# monitor_waterpressure.net
KiCad netlist of a schematic drawn in Altium Designer
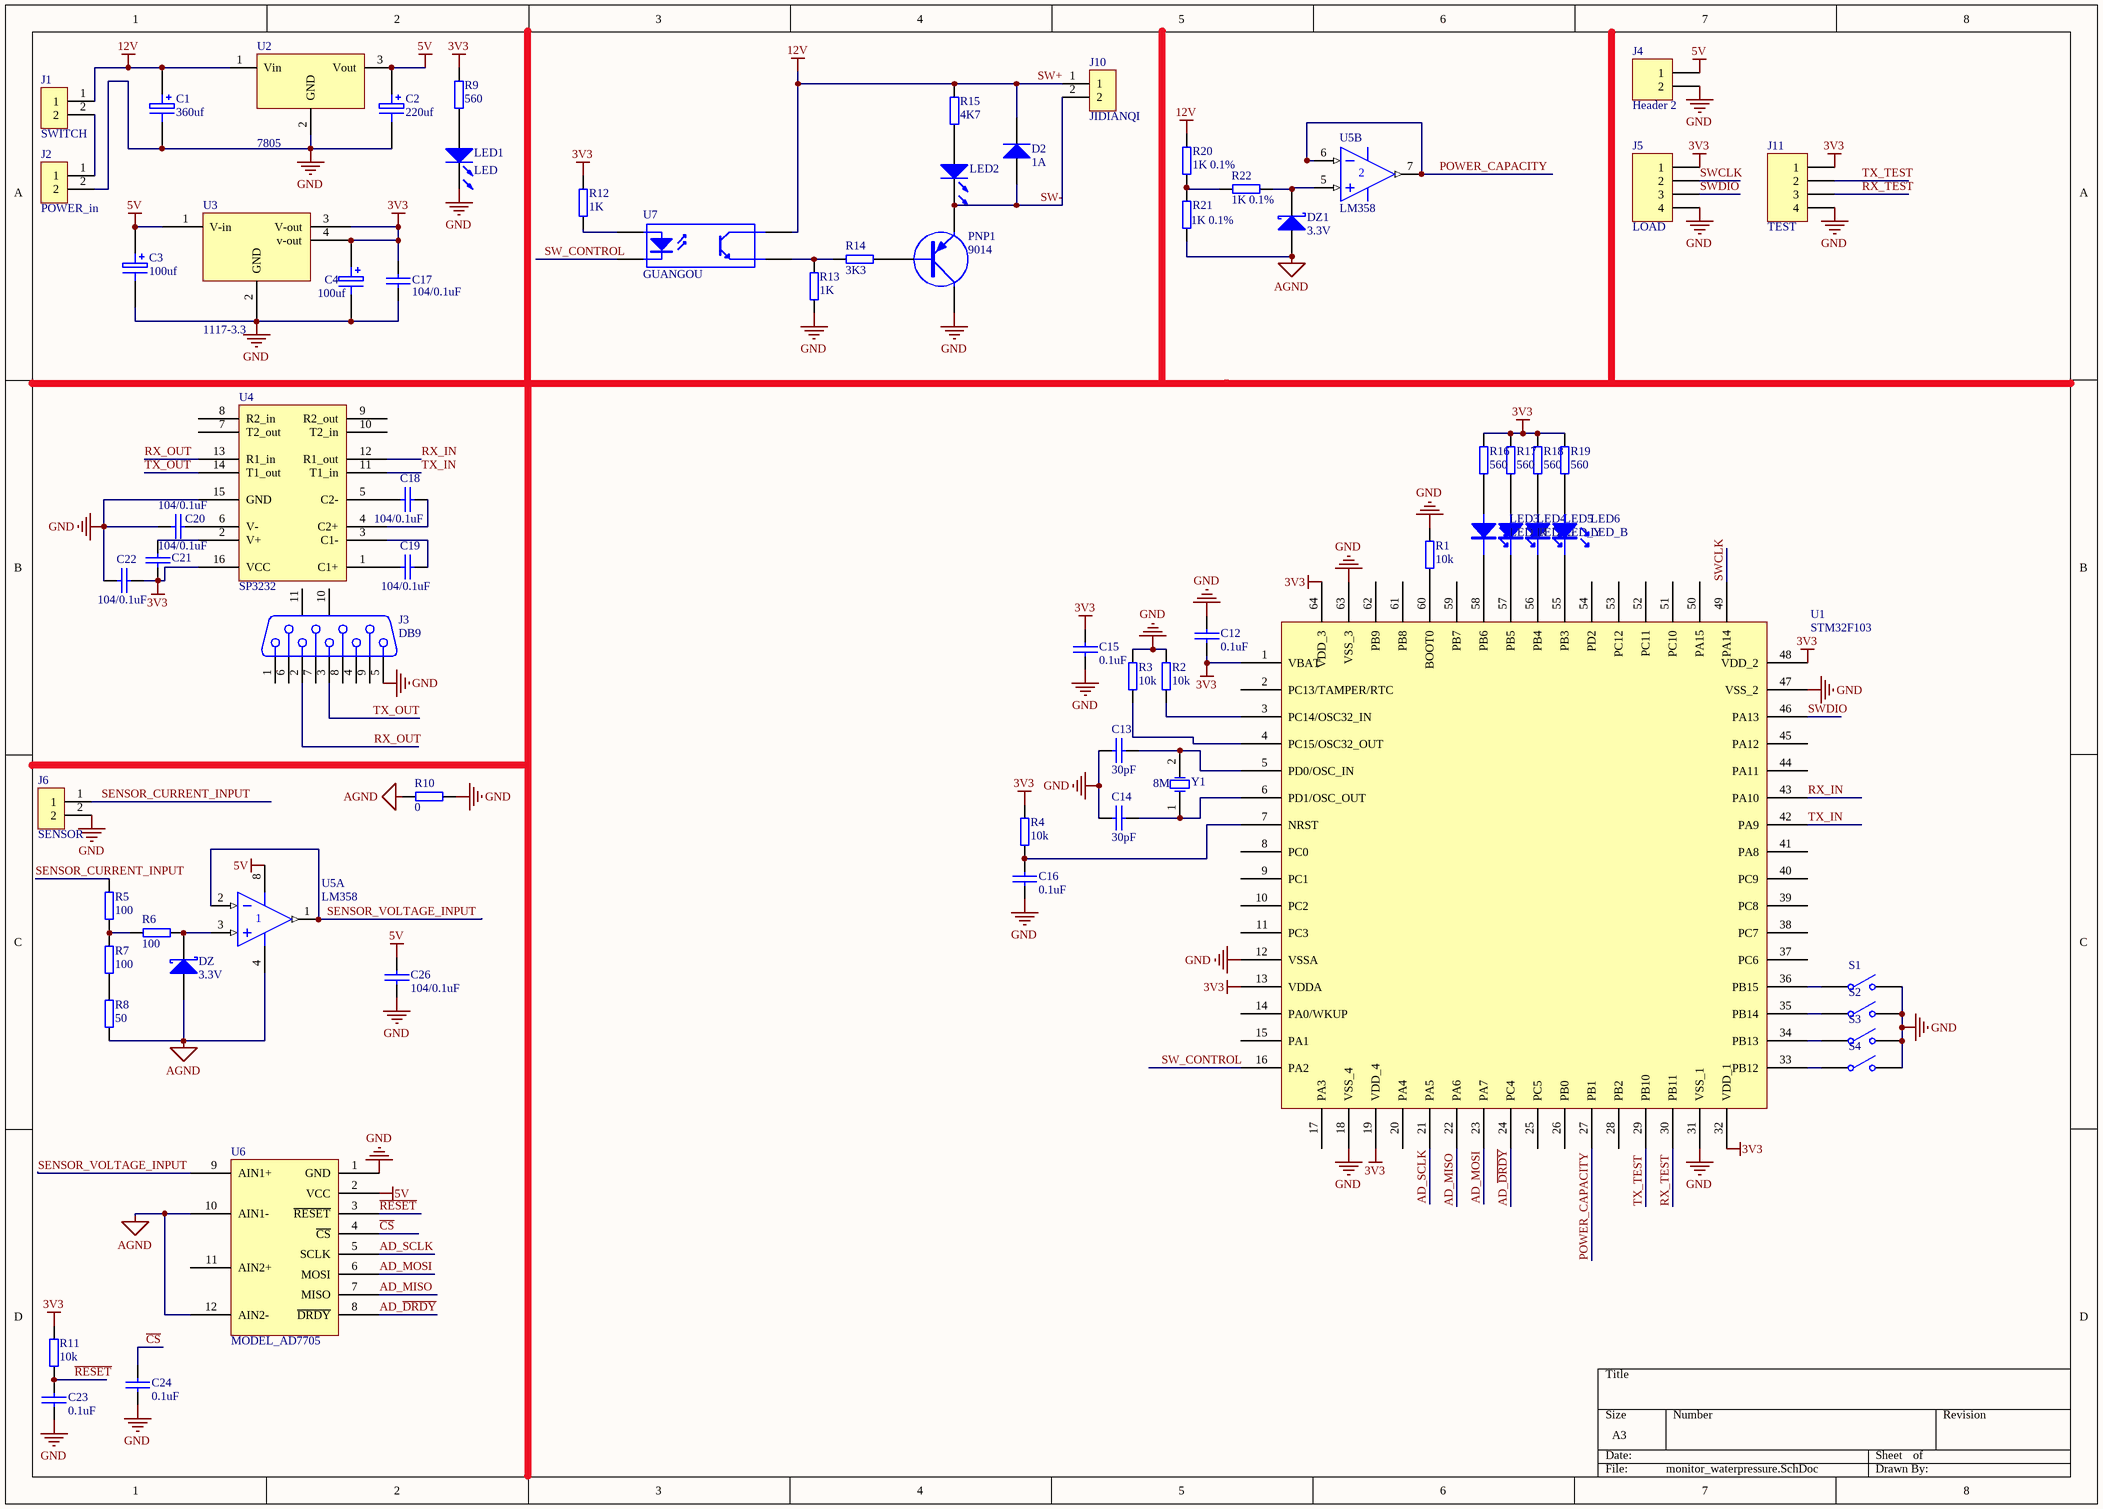
[diagram p0: monitor_waterpressure.SchDoc]

(export (version "E")
  (design (tool "Eeschema 10.0.6"))
  (components
    (comp (ref "C1")
      (value "360uf")
      (footprint "RAD-200-1")
      (description "Electrolytic Capacitor")
      (libsource (lib "PRJ_智能泊车") (part "ELECTRO1"))
    )
    (comp (ref "C2")
      (value "220uf")
      (footprint "RAD-200-1")
      (description "Electrolytic Capacitor")
      (libsource (lib "PRJ_智能泊车") (part "ELECTRO1"))
    )
    (comp (ref "C3")
      (value "100uf")
      (footprint "RAD-200-1")
      (description "Electrolytic Capacitor")
      (libsource (lib "PRJ_智能泊车") (part "ELECTRO1"))
    )
    (comp (ref "C4")
      (value "100uf")
      (footprint "RAD-200-1")
      (description "Electrolytic Capacitor")
      (libsource (lib "PRJ_智能泊车") (part "ELECTRO1"))
    )
    (comp (ref "C12")
      (value "0.1uF")
      (footprint "0805")
      (libsource (lib "hujian-sch2016-05-07") (part "cap"))
    )
    (comp (ref "C13") (value "30pF") (footprint "0805") (libsource (lib "hujian-sch2016-05-07") (part "cap")))
    (comp (ref "C14") (value "30pF") (footprint "0805") (libsource (lib "hujian-sch2016-05-07") (part "cap")))
    (comp (ref "C15")
      (value "0.1uF")
      (footprint "0805")
      (libsource (lib "hujian-sch2016-05-07") (part "cap"))
    )
    (comp (ref "C16")
      (value "0.1uF")
      (footprint "0805")
      (libsource (lib "hujian-sch2016-05-07") (part "cap"))
    )
    (comp (ref "C17")
      (value "104/0.1uF")
      (footprint "0805")
      (libsource (lib "hujian-sch2016-05-07") (part "cap"))
    )
    (comp (ref "C18")
      (value "104/0.1uF")
      (footprint "0805")
      (libsource (lib "hujian-sch2016-05-07") (part "cap"))
    )
    (comp (ref "C19")
      (value "104/0.1uF")
      (footprint "0805")
      (libsource (lib "hujian-sch2016-05-07") (part "cap"))
    )
    (comp (ref "C20")
      (value "104/0.1uF")
      (footprint "0805")
      (libsource (lib "hujian-sch2016-05-07") (part "cap"))
    )
    (comp (ref "C21")
      (value "104/0.1uF")
      (footprint "0805")
      (libsource (lib "hujian-sch2016-05-07") (part "cap"))
    )
    (comp (ref "C22")
      (value "104/0.1uF")
      (footprint "0805")
      (libsource (lib "hujian-sch2016-05-07") (part "cap"))
    )
    (comp (ref "C23")
      (value "0.1uF")
      (footprint "0805")
      (libsource (lib "hujian-sch2016-05-07") (part "cap"))
    )
    (comp (ref "C24")
      (value "0.1uF")
      (footprint "0805")
      (libsource (lib "hujian-sch2016-05-07") (part "cap"))
    )
    (comp (ref "C26")
      (value "104/0.1uF")
      (footprint "0805")
      (libsource (lib "hujian-sch2016-05-07") (part "cap"))
    )
    (comp (ref "D2")
      (value "1A")
      (footprint "ERJIGUAN-1.1MM")
      (libsource (lib "hujian-sch2016-05-07") (part "DIODE"))
    )
    (comp (ref "DZ")
      (value "3.3V")
      (footprint "ERJIGUAN-5")
      (description "Schottky Rectifier")
      (fields (field (name "PUBLISHER") "Altium Limited"))
      (libsource (lib "hujian-sch2016-05-07") (part "Diode_DZ"))
    )
    (comp (ref "DZ1")
      (value "3.3V")
      (footprint "ERJIGUAN-5")
      (description "Schottky Rectifier")
      (fields (field (name "PUBLISHER") "Altium Limited"))
      (libsource (lib "hujian-sch2016-05-07") (part "Diode_DZ"))
    )
    (comp (ref "J1") (value "SWITCH") (footprint "CON2_7.62MM") (libsource (lib "") (part "CON2_1")))
    (comp (ref "J2") (value "POWER_in") (footprint "CON2-100mil-XH") (libsource (lib "") (part "CON2_1")))
    (comp (ref "J3") (value "DB9") (footprint "DB9") (libsource (lib "hujian-sch2016-05-07") (part "DB9")))
    (comp (ref "J4")
      (value "Header 2")
      (footprint "HDR1X2")
      (description "Header, 2-Pin")
      (fields (field (name "PUBLISHER") "Altium Limited"))
      (libsource (lib "Miscellaneous Connectors") (part "Header 2"))
    )
    (comp (ref "J5")
      (value "LOAD")
      (footprint "HDR1X4")
      (description "Header, 4-Pin")
      (fields (field (name "PUBLISHER") "Altium Limited"))
      (libsource (lib "Miscellaneous Connectors") (part "Header 4"))
    )
    (comp (ref "J6") (value "SENSOR") (footprint "CON2-200") (libsource (lib "") (part "CON2_1")))
    (comp (ref "J10")
      (value "JIDIANQI")
      (footprint "CN2_S")
      (libsource (lib "hujian-sch2016-05-07") (part "CON2"))
    )
    (comp (ref "J11")
      (value "TEST")
      (footprint "HDR1X4")
      (description "Header, 4-Pin")
      (fields (field (name "PUBLISHER") "Altium Limited"))
      (libsource (lib "Miscellaneous Connectors") (part "Header 4"))
    )
    (comp (ref "LED1")
      (value "LED")
      (footprint "LED-0805")
      (fields (field (name "PUBLISHER") "Altium Limited"))
      (libsource (lib "hujian-sch2016-05-07") (part "LED"))
    )
    (comp (ref "LED2")
      (value "LED-AK")
      (footprint "LED-0805")
      (fields (field (name "PUBLISHER") "Altium Limited"))
      (libsource (lib "hujian-sch2016-05-07") (part "LED"))
    )
    (comp (ref "LED3") (value "LED_R") (footprint "LED-0805") (libsource (lib "PRJ_智能泊车") (part "LED")))
    (comp (ref "LED4") (value "LED_G") (footprint "LED-0805") (libsource (lib "PRJ_智能泊车") (part "LED")))
    (comp (ref "LED5") (value "LED_Y") (footprint "LED-0805") (libsource (lib "PRJ_智能泊车") (part "LED")))
    (comp (ref "LED6") (value "LED_B") (footprint "LED-0805") (libsource (lib "PRJ_智能泊车") (part "LED")))
    (comp (ref "PNP1")
      (value "9014")
      (footprint "PNP")
      (libsource (lib "hujian-sch2016-05-07") (part "PNP_123"))
    )
    (comp (ref "R1")
      (value "10k")
      (footprint "0805")
      (libsource (lib "hujian-sch2016-05-07") (part "RES2-2"))
    )
    (comp (ref "R2")
      (value "10k")
      (footprint "0805")
      (libsource (lib "hujian-sch2016-05-07") (part "RES2-2"))
    )
    (comp (ref "R3")
      (value "10k")
      (footprint "0805")
      (libsource (lib "hujian-sch2016-05-07") (part "RES2-2"))
    )
    (comp (ref "R4")
      (value "10k")
      (footprint "0805")
      (libsource (lib "hujian-sch2016-05-07") (part "RES2-2"))
    )
    (comp (ref "R5")
      (value "100")
      (footprint "0805")
      (libsource (lib "hujian-sch2016-05-07") (part "RES2-2"))
    )
    (comp (ref "R6")
      (value "100")
      (footprint "0805")
      (libsource (lib "hujian-sch2016-05-07") (part "RES2-2"))
    )
    (comp (ref "R7")
      (value "100")
      (footprint "0805")
      (libsource (lib "hujian-sch2016-05-07") (part "RES2-2"))
    )
    (comp (ref "R8") (value "50") (footprint "0805") (libsource (lib "hujian-sch2016-05-07") (part "RES2-2")))
    (comp (ref "R9")
      (value "560")
      (footprint "0805")
      (libsource (lib "hujian-sch2016-05-07") (part "RES2-2"))
    )
    (comp (ref "R10") (value "0") (footprint "0805") (libsource (lib "hujian-sch2016-05-07") (part "RES2-2")))
    (comp (ref "R11")
      (value "10k")
      (footprint "0805")
      (libsource (lib "hujian-sch2016-05-07") (part "RES2-2"))
    )
    (comp (ref "R12")
      (value "1K")
      (footprint "0805")
      (libsource (lib "hujian-sch2016-05-07") (part "RES2-2"))
    )
    (comp (ref "R13")
      (value "1K")
      (footprint "0805")
      (libsource (lib "hujian-sch2016-05-07") (part "RES2-2"))
    )
    (comp (ref "R14")
      (value "3K3")
      (footprint "0805")
      (libsource (lib "hujian-sch2016-05-07") (part "RES2-2"))
    )
    (comp (ref "R15")
      (value "4K7")
      (footprint "0805")
      (libsource (lib "hujian-sch2016-05-07") (part "RES2-2"))
    )
    (comp (ref "R16")
      (value "560")
      (footprint "0805")
      (libsource (lib "hujian-sch2016-05-07") (part "RES2-2"))
    )
    (comp (ref "R17")
      (value "560")
      (footprint "0805")
      (libsource (lib "hujian-sch2016-05-07") (part "RES2-2"))
    )
    (comp (ref "R18")
      (value "560")
      (footprint "0805")
      (libsource (lib "hujian-sch2016-05-07") (part "RES2-2"))
    )
    (comp (ref "R19")
      (value "560")
      (footprint "0805")
      (libsource (lib "hujian-sch2016-05-07") (part "RES2-2"))
    )
    (comp (ref "R20")
      (value "1K 0.1%")
      (footprint "0805")
      (libsource (lib "hujian-sch2016-05-07") (part "RES2-2"))
    )
    (comp (ref "R21")
      (value "1K 0.1%")
      (footprint "0805")
      (libsource (lib "hujian-sch2016-05-07") (part "RES2-2"))
    )
    (comp (ref "R22")
      (value "1K 0.1%")
      (footprint "0805")
      (libsource (lib "hujian-sch2016-05-07") (part "RES2-2"))
    )
    (comp (ref "S1")
      (value "SW-SPST")
      (footprint "SW_SPST")
      (description "Single-Pole, Single-Throw Switch")
      (fields (field (name "PUBLISHER") "Altium Limited"))
      (libsource (lib "Miscellaneous Devices") (part "SW-SPST"))
    )
    (comp (ref "S2")
      (value "SW-SPST")
      (footprint "SW_SPST")
      (description "Single-Pole, Single-Throw Switch")
      (fields (field (name "PUBLISHER") "Altium Limited"))
      (libsource (lib "Miscellaneous Devices") (part "SW-SPST"))
    )
    (comp (ref "S3")
      (value "SW-SPST")
      (footprint "SW_SPST")
      (description "Single-Pole, Single-Throw Switch")
      (fields (field (name "PUBLISHER") "Altium Limited"))
      (libsource (lib "Miscellaneous Devices") (part "SW-SPST"))
    )
    (comp (ref "S4")
      (value "SW-SPST")
      (footprint "SW_SPST")
      (description "Single-Pole, Single-Throw Switch")
      (fields (field (name "PUBLISHER") "Altium Limited"))
      (libsource (lib "Miscellaneous Devices") (part "SW-SPST"))
    )
    (comp (ref "U1")
      (value "STM32F103")
      (footprint "LQFP-64")
      (libsource (lib "hujian-sch2016-05-07") (part "STM32F103"))
    )
    (comp (ref "U2")
      (value "7805")
      (footprint "TO220")
      (libsource (lib "hujian-sch2016-05-07") (part "7805"))
    )
    (comp (ref "U3")
      (value "1117-3.3")
      (footprint "lm1117-3.3")
      (libsource (lib "hujian-sch2016-05-07") (part "1117-3.3"))
    )
    (comp (ref "U4")
      (value "SP3232")
      (footprint "SO-16")
      (description "U")
      (libsource (lib "hujian-sch2016-05-07") (part "MAX232"))
    )
    (comp (ref "U5")
      (value "LM358")
      (footprint "SO-8")
      (libsource (lib "hujian-sch2016-05-07") (part "LM358"))
    )
    (comp (ref "U6") (value "MODEL_AD7705") (libsource (lib "hujian-sch2016-05-07") (part "MODEL_AD7705")))
    (comp (ref "U7")
      (value "GUANGOU")
      (footprint "TLP521")
      (libsource (lib "hujian-sch2016-05-07") (part "GUANGOU"))
    )
    (comp (ref "Y1") (value "8M") (footprint "XTAL1") (libsource (lib "hujian-sch2016-05-07") (part "晶振")))
  )
  (nets
    (net (code "1") (name "/AD_MISO") (class "Default")
      (node (ref "U1") (pin "22") (pinfunction "PA6_22") (pintype "passive"))
      (node (ref "U6") (pin "7") (pinfunction "MISO_7") (pintype "passive"))
    )
    (net (code "2") (name "/AD_MOSI") (class "Default")
      (node (ref "U1") (pin "23") (pinfunction "PA7_23") (pintype "passive"))
      (node (ref "U6") (pin "6") (pinfunction "MOSI_6") (pintype "passive"))
    )
    (net (code "3") (name "/AD_SCLK") (class "Default")
      (node (ref "U1") (pin "21") (pinfunction "PA5_21") (pintype "passive"))
      (node (ref "U6") (pin "5") (pinfunction "SCLK_5") (pintype "passive"))
    )
    (net (code "4") (name "/AD_~{DRDY}") (class "Default")
      (node (ref "U1") (pin "24") (pinfunction "PC4_24") (pintype "passive"))
      (node (ref "U6") (pin "8") (pinfunction "~{DRDY}_8") (pintype "passive"))
    )
    (net (code "5") (name "/POWER_CAPACITY") (class "Default")
      (node (ref "U1") (pin "27") (pinfunction "PB1_27") (pintype "passive"))
      (node (ref "U5") (pin "6") (pinfunction "IN-_6") (pintype "input"))
      (node (ref "U5") (pin "7") (pinfunction "OUT_7") (pintype "output"))
    )
    (net (code "6") (name "/RX_IN") (class "Default")
      (node (ref "U1") (pin "43") (pinfunction "PA10_43") (pintype "passive"))
      (node (ref "U4") (pin "12") (pinfunction "R1_out_12") (pintype "passive"))
    )
    (net (code "7") (name "/RX_OUT") (class "Default")
      (node (ref "J3") (pin "2") (pinfunction "2_2") (pintype "passive"))
      (node (ref "U4") (pin "13") (pinfunction "R1_in_13") (pintype "passive"))
    )
    (net (code "8") (name "/RX_TEST") (class "Default")
      (node (ref "J11") (pin "3") (pinfunction "3_3") (pintype "passive"))
      (node (ref "U1") (pin "30") (pinfunction "PB11_30") (pintype "passive"))
    )
    (net (code "9") (name "/SENSOR_CURRENT_INPUT") (class "Default")
      (node (ref "J6") (pin "1") (pinfunction "1_1") (pintype "passive"))
      (node (ref "R5") (pin "2") (pinfunction "2_2") (pintype "passive"))
    )
    (net (code "10") (name "/SENSOR_VOLTAGE_INPUT") (class "Default")
      (node (ref "U5") (pin "1") (pinfunction "1_1") (pintype "output"))
      (node (ref "U5") (pin "2") (pinfunction "IN-_2") (pintype "input"))
      (node (ref "U6") (pin "9") (pinfunction "AIN1+_9") (pintype "passive"))
    )
    (net (code "11") (name "/SW-") (class "Default")
      (node (ref "D2") (pin "1") (pinfunction "1_1") (pintype "passive"))
      (node (ref "J10") (pin "2") (pinfunction "2_2") (pintype "passive"))
      (node (ref "LED2") (pin "K") (pinfunction "K_K") (pintype "passive"))
      (node (ref "PNP1") (pin "2") (pinfunction "E_2") (pintype "passive"))
    )
    (net (code "12") (name "/SWCLK") (class "Default")
      (node (ref "J5") (pin "2") (pinfunction "2_2") (pintype "passive"))
      (node (ref "U1") (pin "49") (pinfunction "PA14_49") (pintype "passive"))
    )
    (net (code "13") (name "/SWDIO") (class "Default")
      (node (ref "J5") (pin "3") (pinfunction "3_3") (pintype "passive"))
      (node (ref "U1") (pin "46") (pinfunction "PA13_46") (pintype "passive"))
    )
    (net (code "14") (name "/SW_CONTROL") (class "Default")
      (node (ref "U1") (pin "16") (pinfunction "PA2_16") (pintype "passive"))
      (node (ref "U7") (pin "2") (pinfunction "K_2") (pintype "passive"))
    )
    (net (code "15") (name "/TX_IN") (class "Default")
      (node (ref "U1") (pin "42") (pinfunction "PA9_42") (pintype "passive"))
      (node (ref "U4") (pin "11") (pinfunction "T1_in_11") (pintype "passive"))
    )
    (net (code "16") (name "/TX_OUT") (class "Default")
      (node (ref "J3") (pin "3") (pinfunction "3_3") (pintype "passive"))
      (node (ref "U4") (pin "14") (pinfunction "T1_out_14") (pintype "passive"))
    )
    (net (code "17") (name "/TX_TEST") (class "Default")
      (node (ref "J11") (pin "2") (pinfunction "2_2") (pintype "passive"))
      (node (ref "U1") (pin "29") (pinfunction "PB10_29") (pintype "passive"))
    )
    (net (code "18") (name "/~{CS}") (class "Default")
      (node (ref "C24") (pin "1") (pinfunction "1_1") (pintype "passive"))
      (node (ref "U6") (pin "4") (pinfunction "~{CS}_4") (pintype "passive"))
    )
    (net (code "19") (name "/~{RESET}") (class "Default")
      (node (ref "C23") (pin "1") (pinfunction "1_1") (pintype "passive"))
      (node (ref "R11") (pin "1") (pinfunction "1_1") (pintype "passive"))
      (node (ref "U6") (pin "3") (pinfunction "~{RESET}_3") (pintype "passive"))
    )
    (net (code "20") (name "3V3") (class "Default")
      (node (ref "C12") (pin "2") (pinfunction "2_2") (pintype "passive"))
      (node (ref "C15") (pin "1") (pinfunction "1_1") (pintype "passive"))
      (node (ref "C17") (pin "1") (pinfunction "1_1") (pintype "passive"))
      (node (ref "C21") (pin "1") (pinfunction "1_1") (pintype "passive"))
      (node (ref "C22") (pin "2") (pinfunction "2_2") (pintype "passive"))
      (node (ref "C4") (pin "1") (pinfunction "1_1") (pintype "passive"))
      (node (ref "J11") (pin "1") (pinfunction "1_1") (pintype "passive"))
      (node (ref "J5") (pin "1") (pinfunction "1_1") (pintype "passive"))
      (node (ref "R11") (pin "2") (pinfunction "2_2") (pintype "passive"))
      (node (ref "R12") (pin "2") (pinfunction "2_2") (pintype "passive"))
      (node (ref "R16") (pin "1") (pinfunction "1_1") (pintype "passive"))
      (node (ref "R17") (pin "1") (pinfunction "1_1") (pintype "passive"))
      (node (ref "R18") (pin "2") (pinfunction "2_2") (pintype "passive"))
      (node (ref "R19") (pin "2") (pinfunction "2_2") (pintype "passive"))
      (node (ref "R4") (pin "2") (pinfunction "2_2") (pintype "passive"))
      (node (ref "R9") (pin "2") (pinfunction "2_2") (pintype "passive"))
      (node (ref "U1") (pin "1") (pinfunction "VBAT_1") (pintype "passive"))
      (node (ref "U1") (pin "13") (pinfunction "VDDA_13") (pintype "passive"))
      (node (ref "U1") (pin "19") (pinfunction "VDD_4_19") (pintype "passive"))
      (node (ref "U1") (pin "32") (pinfunction "VDD_1_32") (pintype "passive"))
      (node (ref "U1") (pin "48") (pinfunction "VDD_2_48") (pintype "passive"))
      (node (ref "U1") (pin "64") (pinfunction "VDD_3_64") (pintype "passive"))
      (node (ref "U3") (pin "3") (pinfunction "V-out_3") (pintype "passive"))
      (node (ref "U3") (pin "4") (pinfunction "v-out_4") (pintype "passive"))
      (node (ref "U4") (pin "16") (pinfunction "VCC_16") (pintype "passive"))
    )
    (net (code "21") (name "5V") (class "Default")
      (node (ref "C2") (pin "1") (pinfunction "1_1") (pintype "passive"))
      (node (ref "C26") (pin "1") (pinfunction "1_1") (pintype "passive"))
      (node (ref "C3") (pin "1") (pinfunction "1_1") (pintype "passive"))
      (node (ref "J4") (pin "1") (pinfunction "1_1") (pintype "passive"))
      (node (ref "U2") (pin "3") (pinfunction "Vout_3") (pintype "passive"))
      (node (ref "U3") (pin "1") (pinfunction "V-in_1") (pintype "passive"))
      (node (ref "U5") (pin "8") (pinfunction "V+_8") (pintype "power_in"))
      (node (ref "U6") (pin "2") (pinfunction "VCC_2") (pintype "passive"))
    )
    (net (code "22") (name "12V") (class "Default")
      (node (ref "C1") (pin "1") (pinfunction "1_1") (pintype "passive"))
      (node (ref "D2") (pin "2") (pinfunction "2_2") (pintype "passive"))
      (node (ref "J1") (pin "1") (pinfunction "1_1") (pintype "passive"))
      (node (ref "J10") (pin "1") (pinfunction "1_1") (pintype "passive"))
      (node (ref "R15") (pin "2") (pinfunction "2_2") (pintype "passive"))
      (node (ref "R20") (pin "2") (pinfunction "2_2") (pintype "passive"))
      (node (ref "U2") (pin "1") (pinfunction "Vin_1") (pintype "passive"))
      (node (ref "U7") (pin "4") (pinfunction "C_4") (pintype "passive"))
    )
    (net (code "23") (name "AGND") (class "Default")
      (node (ref "DZ") (pin "1") (pinfunction "A_1") (pintype "passive"))
      (node (ref "DZ1") (pin "1") (pinfunction "A_1") (pintype "passive"))
      (node (ref "R10") (pin "2") (pinfunction "2_2") (pintype "passive"))
      (node (ref "R21") (pin "1") (pinfunction "1_1") (pintype "passive"))
      (node (ref "R8") (pin "1") (pinfunction "1_1") (pintype "passive"))
      (node (ref "U5") (pin "4") (pinfunction "V-_4") (pintype "power_in"))
      (node (ref "U6") (pin "10") (pinfunction "AIN1-_10") (pintype "passive"))
      (node (ref "U6") (pin "12") (pinfunction "AIN2-_12") (pintype "passive"))
    )
    (net (code "24") (name "GND") (class "Default")
      (node (ref "C1") (pin "2") (pinfunction "2_2") (pintype "passive"))
      (node (ref "C12") (pin "1") (pinfunction "1_1") (pintype "passive"))
      (node (ref "C13") (pin "1") (pinfunction "1_1") (pintype "passive"))
      (node (ref "C14") (pin "1") (pinfunction "1_1") (pintype "passive"))
      (node (ref "C15") (pin "2") (pinfunction "2_2") (pintype "passive"))
      (node (ref "C16") (pin "2") (pinfunction "2_2") (pintype "passive"))
      (node (ref "C17") (pin "2") (pinfunction "2_2") (pintype "passive"))
      (node (ref "C2") (pin "2") (pinfunction "2_2") (pintype "passive"))
      (node (ref "C20") (pin "1") (pinfunction "1_1") (pintype "passive"))
      (node (ref "C22") (pin "1") (pinfunction "1_1") (pintype "passive"))
      (node (ref "C23") (pin "2") (pinfunction "2_2") (pintype "passive"))
      (node (ref "C24") (pin "2") (pinfunction "2_2") (pintype "passive"))
      (node (ref "C26") (pin "2") (pinfunction "2_2") (pintype "passive"))
      (node (ref "C3") (pin "2") (pinfunction "2_2") (pintype "passive"))
      (node (ref "C4") (pin "2") (pinfunction "2_2") (pintype "passive"))
      (node (ref "J11") (pin "4") (pinfunction "4_4") (pintype "passive"))
      (node (ref "J2") (pin "2") (pinfunction "2_2") (pintype "passive"))
      (node (ref "J3") (pin "5") (pinfunction "5_5") (pintype "passive"))
      (node (ref "J4") (pin "2") (pinfunction "2_2") (pintype "passive"))
      (node (ref "J5") (pin "4") (pinfunction "4_4") (pintype "passive"))
      (node (ref "J6") (pin "2") (pinfunction "2_2") (pintype "passive"))
      (node (ref "LED1") (pin "K") (pinfunction "K_K") (pintype "passive"))
      (node (ref "PNP1") (pin "3") (pinfunction "C_3") (pintype "passive"))
      (node (ref "R1") (pin "2") (pinfunction "2_2") (pintype "passive"))
      (node (ref "R10") (pin "1") (pinfunction "1_1") (pintype "passive"))
      (node (ref "R13") (pin "1") (pinfunction "1_1") (pintype "passive"))
      (node (ref "R2") (pin "2") (pinfunction "2_2") (pintype "passive"))
      (node (ref "R3") (pin "2") (pinfunction "2_2") (pintype "passive"))
      (node (ref "S1") (pin "2") (pinfunction "NO_2") (pintype "passive"))
      (node (ref "S2") (pin "2") (pinfunction "NO_2") (pintype "passive"))
      (node (ref "S3") (pin "2") (pinfunction "NO_2") (pintype "passive"))
      (node (ref "S4") (pin "2") (pinfunction "NO_2") (pintype "passive"))
      (node (ref "U1") (pin "12") (pinfunction "VSSA_12") (pintype "passive"))
      (node (ref "U1") (pin "18") (pinfunction "VSS_4_18") (pintype "passive"))
      (node (ref "U1") (pin "31") (pinfunction "VSS_1_31") (pintype "passive"))
      (node (ref "U1") (pin "47") (pinfunction "VSS_2_47") (pintype "passive"))
      (node (ref "U1") (pin "63") (pinfunction "VSS_3_63") (pintype "passive"))
      (node (ref "U2") (pin "2") (pinfunction "GND_2") (pintype "passive"))
      (node (ref "U3") (pin "2") (pinfunction "GND_2") (pintype "passive"))
      (node (ref "U4") (pin "15") (pinfunction "GND_15") (pintype "passive"))
      (node (ref "U6") (pin "1") (pinfunction "GND_1") (pintype "passive"))
    )
    (net (code "25") (name "Net-(DZ-K)") (class "Default")
      (node (ref "DZ") (pin "2") (pinfunction "K_2") (pintype "passive"))
      (node (ref "R6") (pin "2") (pinfunction "2_2") (pintype "passive"))
      (node (ref "U5") (pin "3") (pinfunction "IN+_3") (pintype "input"))
    )
    (net (code "26") (name "Net-(DZ1-K)") (class "Default")
      (node (ref "DZ1") (pin "2") (pinfunction "K_2") (pintype "passive"))
      (node (ref "R22") (pin "2") (pinfunction "2_2") (pintype "passive"))
      (node (ref "U5") (pin "5") (pinfunction "IN+_5") (pintype "input"))
    )
    (net (code "27") (name "Net-(J1-Pad2)") (class "Default")
      (node (ref "J1") (pin "2") (pinfunction "2_2") (pintype "passive"))
      (node (ref "J2") (pin "1") (pinfunction "1_1") (pintype "passive"))
    )
    (net (code "28") (name "Net-(LED1-PadA)") (class "Default")
      (node (ref "LED1") (pin "A") (pinfunction "A_A") (pintype "passive"))
      (node (ref "R9") (pin "1") (pinfunction "1_1") (pintype "passive"))
    )
    (net (code "29") (name "Net-(LED2-PadA)") (class "Default")
      (node (ref "LED2") (pin "A") (pinfunction "A_A") (pintype "passive"))
      (node (ref "R15") (pin "1") (pinfunction "1_1") (pintype "passive"))
    )
    (net (code "30") (name "Net-(LED3-1)") (class "Default")
      (node (ref "LED3") (pin "A") (pinfunction "1_A") (pintype "passive"))
      (node (ref "R16") (pin "2") (pinfunction "2_2") (pintype "passive"))
    )
    (net (code "31") (name "Net-(LED3-2)") (class "Default")
      (node (ref "LED3") (pin "K") (pinfunction "2_K") (pintype "passive"))
      (node (ref "U1") (pin "58") (pinfunction "PB6_58") (pintype "passive"))
    )
    (net (code "32") (name "Net-(LED4-1)") (class "Default")
      (node (ref "LED4") (pin "A") (pinfunction "1_A") (pintype "passive"))
      (node (ref "R17") (pin "2") (pinfunction "2_2") (pintype "passive"))
    )
    (net (code "33") (name "Net-(LED4-2)") (class "Default")
      (node (ref "LED4") (pin "K") (pinfunction "2_K") (pintype "passive"))
      (node (ref "U1") (pin "57") (pinfunction "PB5_57") (pintype "passive"))
    )
    (net (code "34") (name "Net-(LED5-1)") (class "Default")
      (node (ref "LED5") (pin "A") (pinfunction "1_A") (pintype "passive"))
      (node (ref "R18") (pin "1") (pinfunction "1_1") (pintype "passive"))
    )
    (net (code "35") (name "Net-(LED5-2)") (class "Default")
      (node (ref "LED5") (pin "K") (pinfunction "2_K") (pintype "passive"))
      (node (ref "U1") (pin "56") (pinfunction "PB4_56") (pintype "passive"))
    )
    (net (code "36") (name "Net-(LED6-1)") (class "Default")
      (node (ref "LED6") (pin "A") (pinfunction "1_A") (pintype "passive"))
      (node (ref "R19") (pin "1") (pinfunction "1_1") (pintype "passive"))
    )
    (net (code "37") (name "Net-(LED6-2)") (class "Default")
      (node (ref "LED6") (pin "K") (pinfunction "2_K") (pintype "passive"))
      (node (ref "U1") (pin "55") (pinfunction "PB3_55") (pintype "passive"))
    )
    (net (code "38") (name "Net-(PNP1-B)") (class "Default")
      (node (ref "PNP1") (pin "1") (pinfunction "B_1") (pintype "passive"))
      (node (ref "R14") (pin "1") (pinfunction "1_1") (pintype "passive"))
    )
    (net (code "39") (name "Net-(R5-Pad1)") (class "Default")
      (node (ref "R5") (pin "1") (pinfunction "1_1") (pintype "passive"))
      (node (ref "R6") (pin "1") (pinfunction "1_1") (pintype "passive"))
      (node (ref "R7") (pin "2") (pinfunction "2_2") (pintype "passive"))
    )
    (net (code "40") (name "Net-(R7-Pad1)") (class "Default")
      (node (ref "R7") (pin "1") (pinfunction "1_1") (pintype "passive"))
      (node (ref "R8") (pin "2") (pinfunction "2_2") (pintype "passive"))
    )
    (net (code "41") (name "Net-(R20-Pad1)") (class "Default")
      (node (ref "R20") (pin "1") (pinfunction "1_1") (pintype "passive"))
      (node (ref "R21") (pin "2") (pinfunction "2_2") (pintype "passive"))
      (node (ref "R22") (pin "1") (pinfunction "1_1") (pintype "passive"))
    )
    (net (code "42") (name "Net-(S1-COMMON)") (class "Default")
      (node (ref "S1") (pin "1") (pinfunction "COMMON_1") (pintype "passive"))
      (node (ref "U1") (pin "36") (pinfunction "PB15_36") (pintype "passive"))
    )
    (net (code "43") (name "Net-(S2-COMMON)") (class "Default")
      (node (ref "S2") (pin "1") (pinfunction "COMMON_1") (pintype "passive"))
      (node (ref "U1") (pin "35") (pinfunction "PB14_35") (pintype "passive"))
    )
    (net (code "44") (name "Net-(S3-COMMON)") (class "Default")
      (node (ref "S3") (pin "1") (pinfunction "COMMON_1") (pintype "passive"))
      (node (ref "U1") (pin "34") (pinfunction "PB13_34") (pintype "passive"))
    )
    (net (code "45") (name "Net-(S4-COMMON)") (class "Default")
      (node (ref "S4") (pin "1") (pinfunction "COMMON_1") (pintype "passive"))
      (node (ref "U1") (pin "33") (pinfunction "PB12_33") (pintype "passive"))
    )
    (net (code "46") (name "Net-(U1-BOOT0)") (class "Default")
      (node (ref "R1") (pin "1") (pinfunction "1_1") (pintype "passive"))
      (node (ref "U1") (pin "60") (pinfunction "BOOT0_60") (pintype "passive"))
    )
    (net (code "47") (name "Net-(U1-NRST)") (class "Default")
      (node (ref "C16") (pin "1") (pinfunction "1_1") (pintype "passive"))
      (node (ref "R4") (pin "1") (pinfunction "1_1") (pintype "passive"))
      (node (ref "U1") (pin "7") (pinfunction "NRST_7") (pintype "passive"))
    )
    (net (code "48") (name "Net-(U1-PC14{slash}OSC32_IN)") (class "Default")
      (node (ref "R2") (pin "1") (pinfunction "1_1") (pintype "passive"))
      (node (ref "U1") (pin "3") (pinfunction "PC14/OSC32_IN_3") (pintype "passive"))
    )
    (net (code "49") (name "Net-(U1-PC15{slash}OSC32_OUT)") (class "Default")
      (node (ref "R3") (pin "1") (pinfunction "1_1") (pintype "passive"))
      (node (ref "U1") (pin "4") (pinfunction "PC15/OSC32_OUT_4") (pintype "passive"))
    )
    (net (code "50") (name "Net-(U1-PD0{slash}OSC_IN)") (class "Default")
      (node (ref "C13") (pin "2") (pinfunction "2_2") (pintype "passive"))
      (node (ref "U1") (pin "5") (pinfunction "PD0/OSC_IN_5") (pintype "passive"))
      (node (ref "Y1") (pin "2") (pinfunction "OSC2_2") (pintype "passive"))
    )
    (net (code "51") (name "Net-(U1-PD1{slash}OSC_OUT)") (class "Default")
      (node (ref "C14") (pin "2") (pinfunction "2_2") (pintype "passive"))
      (node (ref "U1") (pin "6") (pinfunction "PD1/OSC_OUT_6") (pintype "passive"))
      (node (ref "Y1") (pin "1") (pinfunction "OSC1_1") (pintype "passive"))
    )
    (net (code "52") (name "Net-(U4-C1+)") (class "Default")
      (node (ref "C19") (pin "1") (pinfunction "1_1") (pintype "passive"))
      (node (ref "U4") (pin "1") (pinfunction "C1+_1") (pintype "passive"))
    )
    (net (code "53") (name "Net-(U4-C1-)") (class "Default")
      (node (ref "C19") (pin "2") (pinfunction "2_2") (pintype "passive"))
      (node (ref "U4") (pin "3") (pinfunction "C1-_3") (pintype "passive"))
    )
    (net (code "54") (name "Net-(U4-C2+)") (class "Default")
      (node (ref "C18") (pin "2") (pinfunction "2_2") (pintype "passive"))
      (node (ref "U4") (pin "4") (pinfunction "C2+_4") (pintype "passive"))
    )
    (net (code "55") (name "Net-(U4-C2-)") (class "Default")
      (node (ref "C18") (pin "1") (pinfunction "1_1") (pintype "passive"))
      (node (ref "U4") (pin "5") (pinfunction "C2-_5") (pintype "passive"))
    )
    (net (code "56") (name "Net-(U4-V+)") (class "Default")
      (node (ref "C21") (pin "2") (pinfunction "2_2") (pintype "passive"))
      (node (ref "U4") (pin "2") (pinfunction "V+_2") (pintype "passive"))
    )
    (net (code "57") (name "Net-(U4-V-)") (class "Default")
      (node (ref "C20") (pin "2") (pinfunction "2_2") (pintype "passive"))
      (node (ref "U4") (pin "6") (pinfunction "V-_6") (pintype "passive"))
    )
    (net (code "58") (name "Net-(U7-A)") (class "Default")
      (node (ref "R12") (pin "1") (pinfunction "1_1") (pintype "passive"))
      (node (ref "U7") (pin "1") (pinfunction "A_1") (pintype "passive"))
    )
    (net (code "59") (name "Net-(U7-E)") (class "Default")
      (node (ref "R13") (pin "2") (pinfunction "2_2") (pintype "passive"))
      (node (ref "R14") (pin "2") (pinfunction "2_2") (pintype "passive"))
      (node (ref "U7") (pin "3") (pinfunction "E_3") (pintype "passive"))
    )
    (net (code "60") (name "unconnected-(J3-MH1-Pad10)") (class "Default")
      (node (ref "J3") (pin "10") (pinfunction "MH1_10") (pintype "passive"))
    )
    (net (code "61") (name "unconnected-(J3-MH2-Pad11)") (class "Default")
      (node (ref "J3") (pin "11") (pinfunction "MH2_11") (pintype "passive"))
    )
    (net (code "62") (name "unconnected-(J3-Pad1)") (class "Default")
      (node (ref "J3") (pin "1") (pinfunction "1_1") (pintype "passive"))
    )
    (net (code "63") (name "unconnected-(J3-Pad4)") (class "Default")
      (node (ref "J3") (pin "4") (pinfunction "4_4") (pintype "passive"))
    )
    (net (code "64") (name "unconnected-(J3-Pad6)") (class "Default")
      (node (ref "J3") (pin "6") (pinfunction "6_6") (pintype "passive"))
    )
    (net (code "65") (name "unconnected-(J3-Pad7)") (class "Default")
      (node (ref "J3") (pin "7") (pinfunction "7_7") (pintype "passive"))
    )
    (net (code "66") (name "unconnected-(J3-Pad8)") (class "Default")
      (node (ref "J3") (pin "8") (pinfunction "8_8") (pintype "passive"))
    )
    (net (code "67") (name "unconnected-(J3-Pad9)") (class "Default")
      (node (ref "J3") (pin "9") (pinfunction "9_9") (pintype "passive"))
    )
    (net (code "68") (name "unconnected-(U1-PA0{slash}WKUP-Pad14)") (class "Default")
      (node (ref "U1") (pin "14") (pinfunction "PA0/WKUP_14") (pintype "passive"))
    )
    (net (code "69") (name "unconnected-(U1-PA1-Pad15)") (class "Default")
      (node (ref "U1") (pin "15") (pinfunction "PA1_15") (pintype "passive"))
    )
    (net (code "70") (name "unconnected-(U1-PA3-Pad17)") (class "Default")
      (node (ref "U1") (pin "17") (pinfunction "PA3_17") (pintype "passive"))
    )
    (net (code "71") (name "unconnected-(U1-PA4-Pad20)") (class "Default")
      (node (ref "U1") (pin "20") (pinfunction "PA4_20") (pintype "passive"))
    )
    (net (code "72") (name "unconnected-(U1-PA8-Pad41)") (class "Default")
      (node (ref "U1") (pin "41") (pinfunction "PA8_41") (pintype "passive"))
    )
    (net (code "73") (name "unconnected-(U1-PA11-Pad44)") (class "Default")
      (node (ref "U1") (pin "44") (pinfunction "PA11_44") (pintype "passive"))
    )
    (net (code "74") (name "unconnected-(U1-PA12-Pad45)") (class "Default")
      (node (ref "U1") (pin "45") (pinfunction "PA12_45") (pintype "passive"))
    )
    (net (code "75") (name "unconnected-(U1-PA15-Pad50)") (class "Default")
      (node (ref "U1") (pin "50") (pinfunction "PA15_50") (pintype "passive"))
    )
    (net (code "76") (name "unconnected-(U1-PB0-Pad26)") (class "Default")
      (node (ref "U1") (pin "26") (pinfunction "PB0_26") (pintype "passive"))
    )
    (net (code "77") (name "unconnected-(U1-PB2-Pad28)") (class "Default")
      (node (ref "U1") (pin "28") (pinfunction "PB2_28") (pintype "passive"))
    )
    (net (code "78") (name "unconnected-(U1-PB7-Pad59)") (class "Default")
      (node (ref "U1") (pin "59") (pinfunction "PB7_59") (pintype "passive"))
    )
    (net (code "79") (name "unconnected-(U1-PB8-Pad61)") (class "Default")
      (node (ref "U1") (pin "61") (pinfunction "PB8_61") (pintype "passive"))
    )
    (net (code "80") (name "unconnected-(U1-PB9-Pad62)") (class "Default")
      (node (ref "U1") (pin "62") (pinfunction "PB9_62") (pintype "passive"))
    )
    (net (code "81") (name "unconnected-(U1-PC0-Pad8)") (class "Default")
      (node (ref "U1") (pin "8") (pinfunction "PC0_8") (pintype "passive"))
    )
    (net (code "82") (name "unconnected-(U1-PC1-Pad9)") (class "Default")
      (node (ref "U1") (pin "9") (pinfunction "PC1_9") (pintype "passive"))
    )
    (net (code "83") (name "unconnected-(U1-PC2-Pad10)") (class "Default")
      (node (ref "U1") (pin "10") (pinfunction "PC2_10") (pintype "passive"))
    )
    (net (code "84") (name "unconnected-(U1-PC3-Pad11)") (class "Default")
      (node (ref "U1") (pin "11") (pinfunction "PC3_11") (pintype "passive"))
    )
    (net (code "85") (name "unconnected-(U1-PC5-Pad25)") (class "Default")
      (node (ref "U1") (pin "25") (pinfunction "PC5_25") (pintype "passive"))
    )
    (net (code "86") (name "unconnected-(U1-PC6-Pad37)") (class "Default")
      (node (ref "U1") (pin "37") (pinfunction "PC6_37") (pintype "passive"))
    )
    (net (code "87") (name "unconnected-(U1-PC7-Pad38)") (class "Default")
      (node (ref "U1") (pin "38") (pinfunction "PC7_38") (pintype "passive"))
    )
    (net (code "88") (name "unconnected-(U1-PC8-Pad39)") (class "Default")
      (node (ref "U1") (pin "39") (pinfunction "PC8_39") (pintype "passive"))
    )
    (net (code "89") (name "unconnected-(U1-PC9-Pad40)") (class "Default")
      (node (ref "U1") (pin "40") (pinfunction "PC9_40") (pintype "passive"))
    )
    (net (code "90") (name "unconnected-(U1-PC10-Pad51)") (class "Default")
      (node (ref "U1") (pin "51") (pinfunction "PC10_51") (pintype "passive"))
    )
    (net (code "91") (name "unconnected-(U1-PC11-Pad52)") (class "Default")
      (node (ref "U1") (pin "52") (pinfunction "PC11_52") (pintype "passive"))
    )
    (net (code "92") (name "unconnected-(U1-PC12-Pad53)") (class "Default")
      (node (ref "U1") (pin "53") (pinfunction "PC12_53") (pintype "passive"))
    )
    (net (code "93") (name "unconnected-(U1-PC13{slash}TAMPER{slash}RTC-Pad2)") (class "Default")
      (node (ref "U1") (pin "2") (pinfunction "PC13/TAMPER/RTC_2") (pintype "passive"))
    )
    (net (code "94") (name "unconnected-(U1-PD2-Pad54)") (class "Default")
      (node (ref "U1") (pin "54") (pinfunction "PD2_54") (pintype "passive"))
    )
    (net (code "95") (name "unconnected-(U4-R2_in-Pad8)") (class "Default")
      (node (ref "U4") (pin "8") (pinfunction "R2_in_8") (pintype "passive"))
    )
    (net (code "96") (name "unconnected-(U4-R2_out-Pad9)") (class "Default")
      (node (ref "U4") (pin "9") (pinfunction "R2_out_9") (pintype "passive"))
    )
    (net (code "97") (name "unconnected-(U4-T2_in-Pad10)") (class "Default")
      (node (ref "U4") (pin "10") (pinfunction "T2_in_10") (pintype "passive"))
    )
    (net (code "98") (name "unconnected-(U4-T2_out-Pad7)") (class "Default")
      (node (ref "U4") (pin "7") (pinfunction "T2_out_7") (pintype "passive"))
    )
    (net (code "99") (name "unconnected-(U6-AIN2+-Pad11)") (class "Default")
      (node (ref "U6") (pin "11") (pinfunction "AIN2+_11") (pintype "passive"))
    )
  )
)
